# 3_MOTOR.net
KiCad netlist of a schematic drawn in Altium Designer
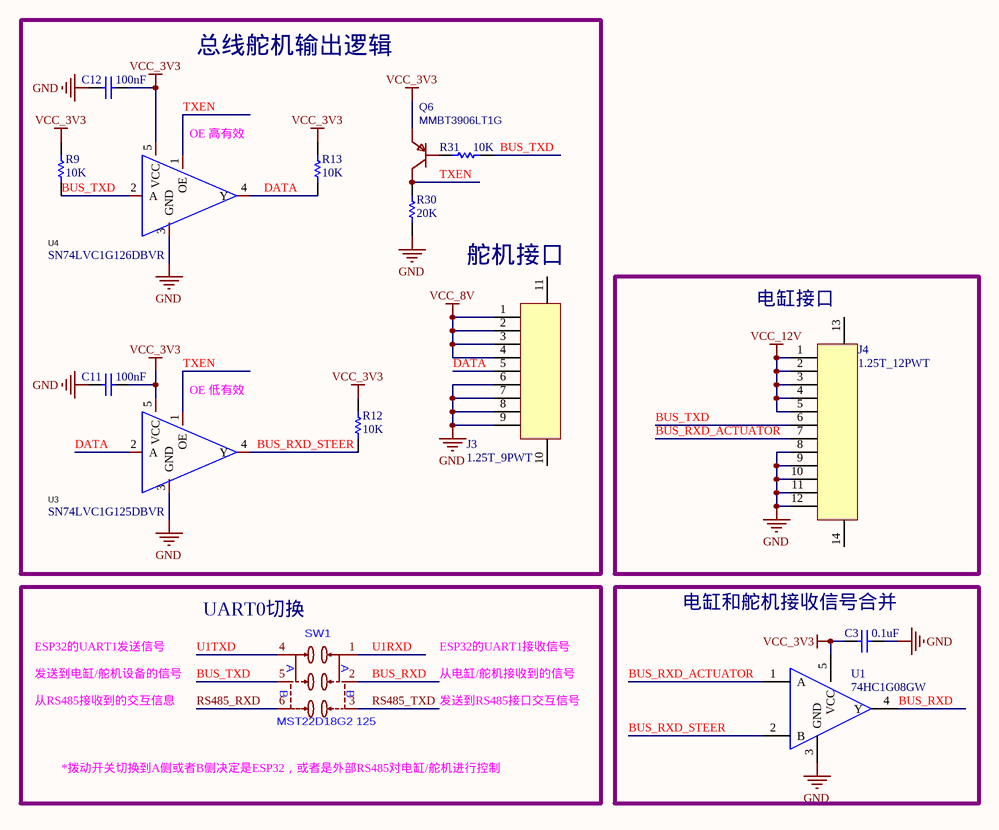
[diagram p0: 3.MOTOR.SchDoc]

(export (version "E")
  (design (tool "Eeschema 10.0.6"))
  (components
    (comp (ref "C3")
      (value "0.1uF")
      (footprint "0402")
      (description "Capacitor")
      (fields (field (name "PARTNUMBER") "CAP100NF") (field (name "PUBLISHER") "Altium Limited"))
      (libsource (lib "Miscellaneous Devices") (part "Cap"))
    )
    (comp (ref "C11")
      (value "100nF")
      (footprint "0402")
      (description "Capacitor")
      (fields (field (name "PARTNUMBER") "CAP100NF") (field (name "PUBLISHER") "Altium Limited"))
      (libsource (lib "Miscellaneous Devices") (part "Cap"))
    )
    (comp (ref "C12")
      (value "100nF")
      (footprint "0402")
      (description "Capacitor")
      (fields (field (name "PARTNUMBER") "CAP100NF") (field (name "PUBLISHER") "Altium Limited"))
      (libsource (lib "Miscellaneous Devices") (part "Cap"))
    )
    (comp (ref "J3")
      (value "1.25T_9PWT")
      (footprint "CONN-SMD_9P-P1.25_SHOU-HAN_1.25-9P-WT")
      (libsource (lib "HM2") (part "1.25T_9P"))
    )
    (comp (ref "J4")
      (value "1.25T_12PWT")
      (footprint "CONN-SMD_12P-P1.25_HCTL_HC-1.25-12PWT")
      (libsource (lib "HM2") (part "1.25T_12P"))
    )
    (comp (ref "Q6")
      (value "MMBT3906LT1G")
      (footprint "SOT-23-3_L2.9-W1.3-P1.90-LS2.4-BR")
      (fields (field (name "BOM_SUPPLIER PART") "C53444") (field (name "CONTRIBUTOR") "LCSC"))
      (libsource (lib "HM2") (part "S8550_C545533"))
    )
    (comp (ref "R9")
      (value "10K")
      (footprint "0402")
      (description "Resistor")
      (fields (field (name "PARTNUMBER") "RES2.2K") (field (name "PUBLISHER") "Altium Limited"))
      (libsource (lib "Miscellaneous Devices") (part "Res1"))
    )
    (comp (ref "R12")
      (value "10K")
      (footprint "0402")
      (description "Resistor")
      (fields (field (name "PARTNUMBER") "RES2.2K") (field (name "PUBLISHER") "Altium Limited"))
      (libsource (lib "Miscellaneous Devices") (part "Res1"))
    )
    (comp (ref "R13")
      (value "10K")
      (footprint "0402")
      (description "Resistor")
      (fields (field (name "PARTNUMBER") "RES2.2K") (field (name "PUBLISHER") "Altium Limited"))
      (libsource (lib "Miscellaneous Devices") (part "Res1"))
    )
    (comp (ref "R30")
      (value "20K")
      (footprint "0402")
      (description "Resistor")
      (fields (field (name "PARTNUMBER") "RES2.2K") (field (name "PUBLISHER") "Altium Limited"))
      (libsource (lib "Miscellaneous Devices") (part "Res1"))
    )
    (comp (ref "R31")
      (value "10K")
      (footprint "0402")
      (description "Resistor")
      (fields (field (name "PARTNUMBER") "RES2.2K") (field (name "PUBLISHER") "Altium Limited"))
      (libsource (lib "Miscellaneous Devices") (part "Res1"))
    )
    (comp (ref "SW1")
      (value "MST22D18G2 125")
      (footprint "SW-SMD_MST22D18G2")
      (libsource (lib "altium-import") (part "root_3_MST22D18G2 125_"))
    )
    (comp (ref "U1")
      (value "74HC1G08GW")
      (footprint "SOT-353_L2.1-W1.3-P0.65-LS2.3-BR")
      (libsource (lib "HM2") (part "74HC1G08"))
    )
    (comp (ref "U3")
      (value "SN74LVC1G125DBVR")
      (footprint "SOT23-5")
      (libsource (lib "HM2") (part "74LVC1G126GW,125"))
    )
    (comp (ref "U4")
      (value "SN74LVC1G126DBVR")
      (footprint "SOT23-5")
      (libsource (lib "HM2") (part "74LVC1G126GW,125"))
    )
  )
  (nets
    (net (code "1") (name "/BUS_RXD") (class "Default")
      (node (ref "SW1") (pin "2") (pinfunction "2_2") (pintype "passive"))
      (node (ref "U1") (pin "4") (pinfunction "Y_4") (pintype "passive"))
    )
    (net (code "2") (name "/BUS_RXD_ACTUATOR") (class "Default")
      (node (ref "J4") (pin "7") (pinfunction "7_7") (pintype "passive"))
      (node (ref "U1") (pin "1") (pinfunction "A_1") (pintype "passive"))
    )
    (net (code "3") (name "/BUS_RXD_STEER") (class "Default")
      (node (ref "R12") (pin "1") (pinfunction "1_1") (pintype "passive"))
      (node (ref "U1") (pin "2") (pinfunction "B_2") (pintype "passive"))
      (node (ref "U3") (pin "4") (pinfunction "Y_4") (pintype "passive"))
    )
    (net (code "4") (name "/BUS_TXD") (class "Default")
      (node (ref "J4") (pin "6") (pinfunction "6_6") (pintype "passive"))
      (node (ref "R31") (pin "1") (pinfunction "1_1") (pintype "passive"))
      (node (ref "R9") (pin "1") (pinfunction "1_1") (pintype "passive"))
      (node (ref "SW1") (pin "5") (pinfunction "5_5") (pintype "passive"))
      (node (ref "U4") (pin "2") (pinfunction "A_2") (pintype "passive"))
    )
    (net (code "5") (name "/DATA") (class "Default")
      (node (ref "J3") (pin "5") (pinfunction "5_5") (pintype "passive"))
      (node (ref "R13") (pin "1") (pinfunction "1_1") (pintype "passive"))
      (node (ref "U3") (pin "2") (pinfunction "A_2") (pintype "passive"))
      (node (ref "U4") (pin "4") (pinfunction "Y_4") (pintype "passive"))
    )
    (net (code "6") (name "/RS485_RXD") (class "Default")
      (node (ref "SW1") (pin "6") (pinfunction "6_6") (pintype "passive"))
    )
    (net (code "7") (name "/RS485_TXD") (class "Default")
      (node (ref "SW1") (pin "3") (pinfunction "3_3") (pintype "passive"))
    )
    (net (code "8") (name "/TXEN") (class "Default")
      (node (ref "Q6") (pin "3") (pinfunction "C_3") (pintype "passive"))
      (node (ref "R30") (pin "1") (pinfunction "1_1") (pintype "passive"))
      (node (ref "U3") (pin "1") (pinfunction "OE_1") (pintype "passive"))
      (node (ref "U4") (pin "1") (pinfunction "OE_1") (pintype "passive"))
    )
    (net (code "9") (name "/U1RXD") (class "Default")
      (node (ref "SW1") (pin "1") (pinfunction "1_1") (pintype "passive"))
    )
    (net (code "10") (name "/U1TXD") (class "Default")
      (node (ref "SW1") (pin "4") (pinfunction "4_4") (pintype "passive"))
    )
    (net (code "11") (name "GND") (class "Default")
      (node (ref "C11") (pin "2") (pinfunction "2_2") (pintype "passive"))
      (node (ref "C12") (pin "2") (pinfunction "2_2") (pintype "passive"))
      (node (ref "C3") (pin "1") (pinfunction "1_1") (pintype "passive"))
      (node (ref "J3") (pin "6") (pinfunction "6_6") (pintype "passive"))
      (node (ref "J3") (pin "7") (pinfunction "7_7") (pintype "passive"))
      (node (ref "J3") (pin "8") (pinfunction "8_8") (pintype "passive"))
      (node (ref "J3") (pin "9") (pinfunction "9_9") (pintype "passive"))
      (node (ref "J4") (pin "10") (pinfunction "10_10") (pintype "passive"))
      (node (ref "J4") (pin "11") (pinfunction "11_11") (pintype "passive"))
      (node (ref "J4") (pin "12") (pinfunction "12_12") (pintype "passive"))
      (node (ref "J4") (pin "8") (pinfunction "8_8") (pintype "passive"))
      (node (ref "J4") (pin "9") (pinfunction "9_9") (pintype "passive"))
      (node (ref "R30") (pin "2") (pinfunction "2_2") (pintype "passive"))
      (node (ref "U1") (pin "3") (pinfunction "GND_3") (pintype "passive"))
      (node (ref "U3") (pin "3") (pinfunction "GND_3") (pintype "passive"))
      (node (ref "U4") (pin "3") (pinfunction "GND_3") (pintype "passive"))
    )
    (net (code "12") (name "Net-(Q6-B)") (class "Default")
      (node (ref "Q6") (pin "1") (pinfunction "B_1") (pintype "passive"))
      (node (ref "R31") (pin "2") (pinfunction "2_2") (pintype "passive"))
    )
    (net (code "13") (name "VCC_3V3") (class "Default")
      (node (ref "C11") (pin "1") (pinfunction "1_1") (pintype "passive"))
      (node (ref "C12") (pin "1") (pinfunction "1_1") (pintype "passive"))
      (node (ref "C3") (pin "2") (pinfunction "2_2") (pintype "passive"))
      (node (ref "Q6") (pin "2") (pinfunction "E_2") (pintype "passive"))
      (node (ref "R12") (pin "2") (pinfunction "2_2") (pintype "passive"))
      (node (ref "R13") (pin "2") (pinfunction "2_2") (pintype "passive"))
      (node (ref "R9") (pin "2") (pinfunction "2_2") (pintype "passive"))
      (node (ref "U1") (pin "5") (pinfunction "VCC_5") (pintype "passive"))
      (node (ref "U3") (pin "5") (pinfunction "VCC_5") (pintype "passive"))
      (node (ref "U4") (pin "5") (pinfunction "VCC_5") (pintype "passive"))
    )
    (net (code "14") (name "VCC_8V") (class "Default")
      (node (ref "J3") (pin "1") (pinfunction "1_1") (pintype "passive"))
      (node (ref "J3") (pin "2") (pinfunction "2_2") (pintype "passive"))
      (node (ref "J3") (pin "3") (pinfunction "3_3") (pintype "passive"))
      (node (ref "J3") (pin "4") (pinfunction "4_4") (pintype "passive"))
    )
    (net (code "15") (name "VCC_12V") (class "Default")
      (node (ref "J4") (pin "1") (pinfunction "1_1") (pintype "passive"))
      (node (ref "J4") (pin "2") (pinfunction "2_2") (pintype "passive"))
      (node (ref "J4") (pin "3") (pinfunction "3_3") (pintype "passive"))
      (node (ref "J4") (pin "4") (pinfunction "4_4") (pintype "passive"))
      (node (ref "J4") (pin "5") (pinfunction "5_5") (pintype "passive"))
    )
    (net (code "16") (name "unconnected-(J3-Pad10)") (class "Default")
      (node (ref "J3") (pin "10") (pinfunction "10_10") (pintype "passive"))
    )
    (net (code "17") (name "unconnected-(J3-Pad11)") (class "Default")
      (node (ref "J3") (pin "11") (pinfunction "11_11") (pintype "passive"))
    )
    (net (code "18") (name "unconnected-(J4-Pad13)") (class "Default")
      (node (ref "J4") (pin "13") (pinfunction "13_13") (pintype "passive"))
    )
    (net (code "19") (name "unconnected-(J4-Pad14)") (class "Default")
      (node (ref "J4") (pin "14") (pinfunction "14_14") (pintype "passive"))
    )
  )
)
